# v1_0.net
KiCad netlist of a schematic drawn in Altium Designer
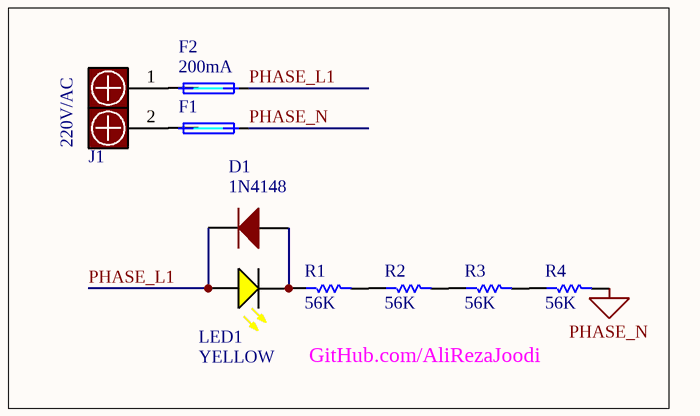
[diagram p0: v1.0.SchDoc]

(export (version "E")
  (design (tool "Eeschema 10.0.6"))
  (components
    (comp (ref "D1")
      (value "1N4148")
      (footprint "SMD_DO-213AA")
      (description "Diode")
      (libsource (lib "General") (part "Diode_2Form"))
    )
    (comp (ref "F1")
      (value "200mA")
      (footprint "SMD_1206")
      (description "Fuse")
      (fields (field (name "1_PART NUMBER") "0437.250WRA"))
      (libsource (lib "General") (part "Fuse"))
    )
    (comp (ref "F2")
      (value "200mA")
      (footprint "SMD_1206")
      (description "Fuse")
      (fields (field (name "1_PART NUMBER") "0437.250WRA"))
      (libsource (lib "General") (part "Fuse"))
    )
    (comp (ref "J1")
      (value "Connector1x2_Power_4Form")
      (footprint "1x2_P8.26")
      (description "Connector, Barrier Terminal Blocks, 2Pin")
      (fields (field (name "1_PART NUMBER") "1977477-2"))
      (libsource (lib "Connector") (part "Connector1x2_Power_4Form"))
    )
    (comp (ref "LED1")
      (value "YELLOW")
      (footprint "SMD_0805_YELLOW")
      (description "LED")
      (libsource (lib "Display") (part "LED_YELLOW"))
    )
    (comp (ref "R1")
      (value "56K")
      (footprint "SMD_0805")
      (description "Resistor, 1/8W, 5%")
      (libsource (lib "General") (part "Resistor"))
    )
    (comp (ref "R2")
      (value "56K")
      (footprint "SMD_0805")
      (description "Resistor, 1/8W, 5%")
      (libsource (lib "General") (part "Resistor"))
    )
    (comp (ref "R3")
      (value "56K")
      (footprint "SMD_0805")
      (description "Resistor, 1/8W, 5%")
      (libsource (lib "General") (part "Resistor"))
    )
    (comp (ref "R4")
      (value "56K")
      (footprint "SMD_0805")
      (description "Resistor, 1/8W, 5%")
      (libsource (lib "General") (part "Resistor"))
    )
  )
  (nets
    (net (code "1") (name "/PHASE_L1") (class "Default")
      (node (ref "D1") (pin "2") (pinfunction "K_2") (pintype "passive"))
      (node (ref "F2") (pin "2") (pinfunction "2_2") (pintype "passive"))
      (node (ref "LED1") (pin "1") (pinfunction "A_1") (pintype "passive"))
    )
    (net (code "2") (name "Net-(D1-A)") (class "Default")
      (node (ref "D1") (pin "1") (pinfunction "A_1") (pintype "passive"))
      (node (ref "LED1") (pin "2") (pinfunction "K_2") (pintype "passive"))
      (node (ref "R1") (pin "2") (pinfunction "2_2") (pintype "passive"))
    )
    (net (code "3") (name "Net-(F1-Pad1)") (class "Default")
      (node (ref "F1") (pin "1") (pinfunction "1_1") (pintype "passive"))
      (node (ref "J1") (pin "2") (pinfunction "2_2") (pintype "passive"))
    )
    (net (code "4") (name "Net-(F2-Pad1)") (class "Default")
      (node (ref "F2") (pin "1") (pinfunction "1_1") (pintype "passive"))
      (node (ref "J1") (pin "1") (pinfunction "1_1") (pintype "passive"))
    )
    (net (code "5") (name "Net-(R1-Pad1)") (class "Default")
      (node (ref "R1") (pin "1") (pinfunction "1_1") (pintype "passive"))
      (node (ref "R2") (pin "2") (pinfunction "2_2") (pintype "passive"))
    )
    (net (code "6") (name "Net-(R2-Pad1)") (class "Default")
      (node (ref "R2") (pin "1") (pinfunction "1_1") (pintype "passive"))
      (node (ref "R3") (pin "2") (pinfunction "2_2") (pintype "passive"))
    )
    (net (code "7") (name "Net-(R3-Pad1)") (class "Default")
      (node (ref "R3") (pin "1") (pinfunction "1_1") (pintype "passive"))
      (node (ref "R4") (pin "2") (pinfunction "2_2") (pintype "passive"))
    )
    (net (code "8") (name "PHASE_N") (class "Default")
      (node (ref "F1") (pin "2") (pinfunction "2_2") (pintype "passive"))
      (node (ref "R4") (pin "1") (pinfunction "1_1") (pintype "passive"))
    )
  )
)
